# demo_IB2.net
KiCad netlist of a schematic drawn in EAGLE
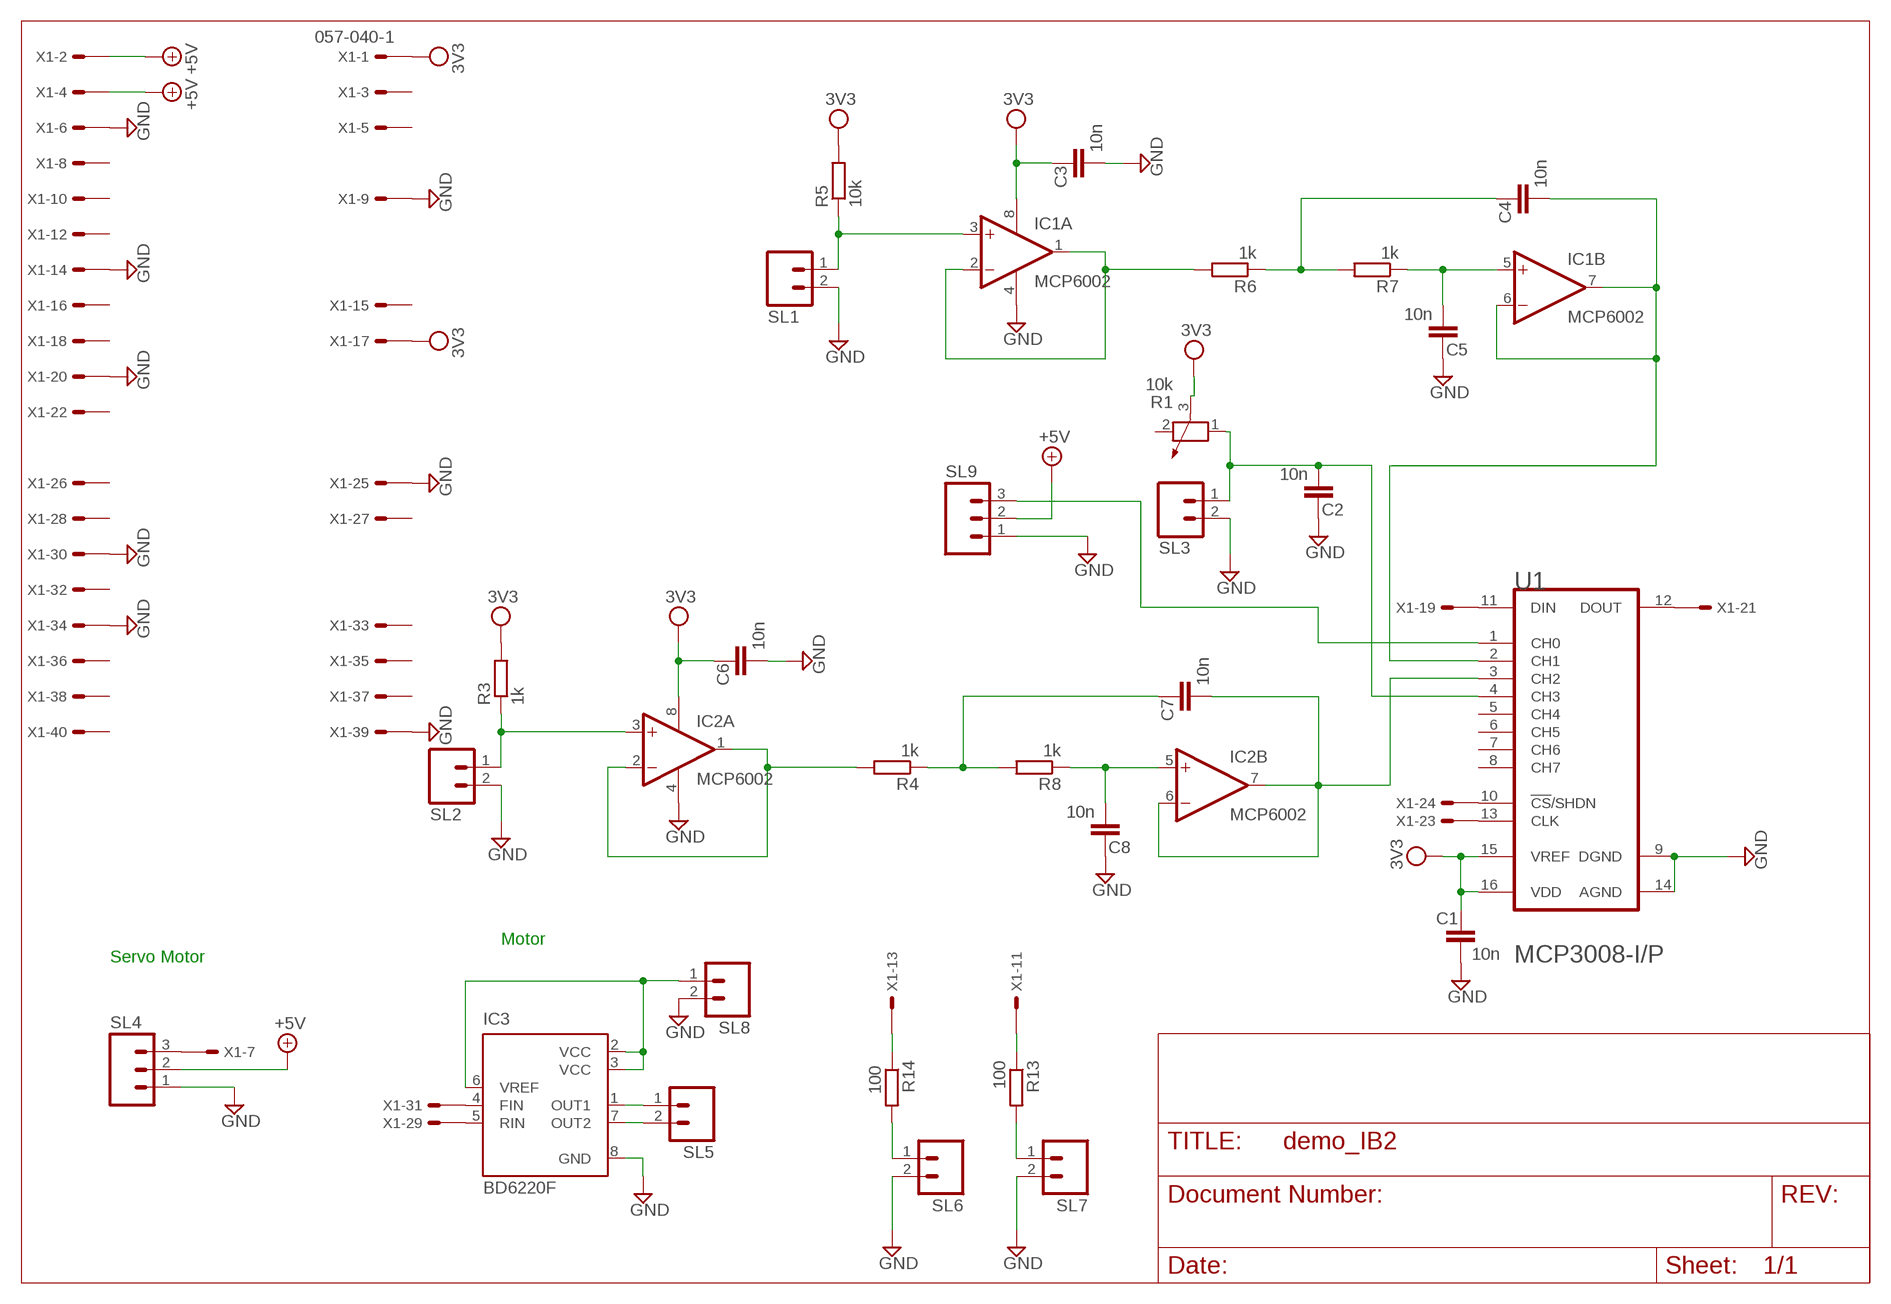
[diagram p0: schematic, sheet 1]

(export (version "E")
  (design (tool "Eeschema 10.0.6"))
  (components
    (comp (ref "C1")
      (value "10n")
      (footprint "eagle-import:C0805")
      (libsource (lib "eagle-import") (part "C-EUC0805"))
    )
    (comp (ref "C2")
      (value "10n")
      (footprint "eagle-import:C0805")
      (libsource (lib "eagle-import") (part "C-EUC0805"))
    )
    (comp (ref "C3")
      (value "10n")
      (footprint "eagle-import:C0805")
      (libsource (lib "eagle-import") (part "C-EUC0805"))
    )
    (comp (ref "C4")
      (value "10n")
      (footprint "eagle-import:C0805")
      (libsource (lib "eagle-import") (part "C-EUC0805"))
    )
    (comp (ref "C5")
      (value "10n")
      (footprint "eagle-import:C0805")
      (libsource (lib "eagle-import") (part "C-EUC0805"))
    )
    (comp (ref "C6")
      (value "10n")
      (footprint "eagle-import:C0805")
      (libsource (lib "eagle-import") (part "C-EUC0805"))
    )
    (comp (ref "C7")
      (value "10n")
      (footprint "eagle-import:C0805")
      (libsource (lib "eagle-import") (part "C-EUC0805"))
    )
    (comp (ref "C8")
      (value "10n")
      (footprint "eagle-import:C0805")
      (libsource (lib "eagle-import") (part "C-EUC0805"))
    )
    (comp (ref "IC1")
      (value "MCP6002")
      (footprint "eagle-import:SO08")
      (libsource (lib "eagle-import") (part "MCP602SN"))
    )
    (comp (ref "IC2")
      (value "MCP6002")
      (footprint "eagle-import:SO08")
      (libsource (lib "eagle-import") (part "MCP602SN"))
    )
    (comp (ref "IC3")
      (value "BD6220F")
      (footprint "eagle-import:SOP8")
      (libsource (lib "eagle-import") (part "BD6220F"))
    )
    (comp (ref "R1")
      (value "10k")
      (footprint "eagle-import:PT-10")
      (libsource (lib "eagle-import") (part "POTENTIOMETER_PT-10"))
    )
    (comp (ref "R3")
      (value "1k")
      (footprint "eagle-import:R0805")
      (libsource (lib "eagle-import") (part "R-EU_R0805"))
    )
    (comp (ref "R4")
      (value "1k")
      (footprint "eagle-import:R0805")
      (libsource (lib "eagle-import") (part "R-EU_R0805"))
    )
    (comp (ref "R5")
      (value "10k")
      (footprint "eagle-import:R0805")
      (libsource (lib "eagle-import") (part "R-EU_R0805"))
    )
    (comp (ref "R6")
      (value "1k")
      (footprint "eagle-import:R0805")
      (libsource (lib "eagle-import") (part "R-EU_R0805"))
    )
    (comp (ref "R7")
      (value "1k")
      (footprint "eagle-import:R0805")
      (libsource (lib "eagle-import") (part "R-EU_R0805"))
    )
    (comp (ref "R8")
      (value "1k")
      (footprint "eagle-import:R0805")
      (libsource (lib "eagle-import") (part "R-EU_R0805"))
    )
    (comp (ref "R13")
      (value "100")
      (footprint "eagle-import:R0805")
      (libsource (lib "eagle-import") (part "R-EU_R0805"))
    )
    (comp (ref "R14")
      (value "100")
      (footprint "eagle-import:R0805")
      (libsource (lib "eagle-import") (part "R-EU_R0805"))
    )
    (comp (ref "SL1")
      (value "M02")
      (footprint "eagle-import:02P")
      (libsource (lib "eagle-import") (part "M02"))
    )
    (comp (ref "SL2")
      (value "M02")
      (footprint "eagle-import:02P")
      (libsource (lib "eagle-import") (part "M02"))
    )
    (comp (ref "SL3")
      (value "M02")
      (footprint "eagle-import:02P")
      (libsource (lib "eagle-import") (part "M02"))
    )
    (comp (ref "SL4")
      (value "M03")
      (footprint "eagle-import:03P")
      (libsource (lib "eagle-import") (part "M03"))
    )
    (comp (ref "SL5")
      (value "M02")
      (footprint "eagle-import:02P")
      (libsource (lib "eagle-import") (part "M02"))
    )
    (comp (ref "SL6")
      (value "M02")
      (footprint "eagle-import:02P")
      (libsource (lib "eagle-import") (part "M02"))
    )
    (comp (ref "SL7")
      (value "M02")
      (footprint "eagle-import:02P")
      (libsource (lib "eagle-import") (part "M02"))
    )
    (comp (ref "SL8")
      (value "M02")
      (footprint "eagle-import:02P")
      (libsource (lib "eagle-import") (part "M02"))
    )
    (comp (ref "SL9")
      (value "M03")
      (footprint "eagle-import:03P")
      (libsource (lib "eagle-import") (part "M03"))
    )
    (comp (ref "U1")
      (value "MICROCHIP_MCP3008-I-P")
      (footprint "eagle-import:SO-16")
      (libsource (lib "eagle-import") (part "MICROCHIP_MCP3008-I-P"))
    )
    (comp (ref "X1")
      (value "057-040-1")
      (footprint "eagle-import:057-040-1")
      (libsource (lib "eagle-import") (part "057-040-1"))
    )
  )
  (nets
    (net (code "1") (name "+5V") (class "Default")
      (node (ref "SL4") (pin "2") (pinfunction "2_2") (pintype "passive"))
      (node (ref "SL9") (pin "2") (pinfunction "2_2") (pintype "passive"))
      (node (ref "X1") (pin "2") (pinfunction "S_2") (pintype "passive"))
      (node (ref "X1") (pin "4") (pinfunction "S_4") (pintype "passive"))
    )
    (net (code "2") (name "3V3") (class "Default")
      (node (ref "C1") (pin "1") (pinfunction "1_1") (pintype "passive"))
      (node (ref "C3") (pin "1") (pinfunction "1_1") (pintype "passive"))
      (node (ref "C6") (pin "1") (pinfunction "1_1") (pintype "passive"))
      (node (ref "IC1") (pin "8") (pinfunction "V+_8") (pintype "power_in"))
      (node (ref "IC2") (pin "8") (pinfunction "V+_8") (pintype "power_in"))
      (node (ref "R1") (pin "3") (pinfunction "3_3") (pintype "passive"))
      (node (ref "R3") (pin "2") (pinfunction "2_2") (pintype "passive"))
      (node (ref "R5") (pin "2") (pinfunction "2_2") (pintype "passive"))
      (node (ref "U1") (pin "15") (pinfunction "VREF_15") (pintype "input"))
      (node (ref "U1") (pin "16") (pinfunction "VDD_16") (pintype "power_in"))
      (node (ref "X1") (pin "1") (pinfunction "S_1") (pintype "passive"))
      (node (ref "X1") (pin "17") (pinfunction "S_17") (pintype "passive"))
    )
    (net (code "3") (name "GND") (class "Default")
      (node (ref "C1") (pin "2") (pinfunction "2_2") (pintype "passive"))
      (node (ref "C2") (pin "1") (pinfunction "1_1") (pintype "passive"))
      (node (ref "C3") (pin "2") (pinfunction "2_2") (pintype "passive"))
      (node (ref "C5") (pin "1") (pinfunction "1_1") (pintype "passive"))
      (node (ref "C6") (pin "2") (pinfunction "2_2") (pintype "passive"))
      (node (ref "C8") (pin "1") (pinfunction "1_1") (pintype "passive"))
      (node (ref "IC1") (pin "4") (pinfunction "V-_4") (pintype "power_in"))
      (node (ref "IC2") (pin "4") (pinfunction "V-_4") (pintype "power_in"))
      (node (ref "IC3") (pin "8") (pinfunction "GND_8") (pintype "power_in"))
      (node (ref "SL1") (pin "2") (pinfunction "2_2") (pintype "passive"))
      (node (ref "SL2") (pin "2") (pinfunction "2_2") (pintype "passive"))
      (node (ref "SL3") (pin "2") (pinfunction "2_2") (pintype "passive"))
      (node (ref "SL4") (pin "1") (pinfunction "1_1") (pintype "passive"))
      (node (ref "SL6") (pin "2") (pinfunction "2_2") (pintype "passive"))
      (node (ref "SL7") (pin "2") (pinfunction "2_2") (pintype "passive"))
      (node (ref "SL8") (pin "2") (pinfunction "2_2") (pintype "passive"))
      (node (ref "SL9") (pin "1") (pinfunction "1_1") (pintype "passive"))
      (node (ref "U1") (pin "14") (pinfunction "AGND_14") (pintype "power_in"))
      (node (ref "U1") (pin "9") (pinfunction "DGND_9") (pintype "power_in"))
      (node (ref "X1") (pin "14") (pinfunction "S_14") (pintype "passive"))
      (node (ref "X1") (pin "20") (pinfunction "S_20") (pintype "passive"))
      (node (ref "X1") (pin "25") (pinfunction "S_25") (pintype "passive"))
      (node (ref "X1") (pin "30") (pinfunction "S_30") (pintype "passive"))
      (node (ref "X1") (pin "34") (pinfunction "S_34") (pintype "passive"))
      (node (ref "X1") (pin "39") (pinfunction "S_39") (pintype "passive"))
      (node (ref "X1") (pin "6") (pinfunction "S_6") (pintype "passive"))
      (node (ref "X1") (pin "9") (pinfunction "S_9") (pintype "passive"))
    )
    (net (code "4") (name "Net-(C4-Pad1)") (class "Default")
      (node (ref "C4") (pin "1") (pinfunction "1_1") (pintype "passive"))
      (node (ref "R6") (pin "1") (pinfunction "1_1") (pintype "passive"))
      (node (ref "R7") (pin "2") (pinfunction "2_2") (pintype "passive"))
    )
    (net (code "5") (name "Net-(C7-Pad1)") (class "Default")
      (node (ref "C7") (pin "1") (pinfunction "1_1") (pintype "passive"))
      (node (ref "R4") (pin "1") (pinfunction "1_1") (pintype "passive"))
      (node (ref "R8") (pin "2") (pinfunction "2_2") (pintype "passive"))
    )
    (net (code "6") (name "Net-(IC1A-+IN)") (class "Default")
      (node (ref "IC1") (pin "3") (pinfunction "+IN_3") (pintype "input"))
      (node (ref "R5") (pin "1") (pinfunction "1_1") (pintype "passive"))
      (node (ref "SL1") (pin "1") (pinfunction "1_1") (pintype "passive"))
    )
    (net (code "7") (name "Net-(IC1A--IN)") (class "Default")
      (node (ref "IC1") (pin "1") (pinfunction "OUT_1") (pintype "output"))
      (node (ref "IC1") (pin "2") (pinfunction "-IN_2") (pintype "input"))
      (node (ref "R6") (pin "2") (pinfunction "2_2") (pintype "passive"))
    )
    (net (code "8") (name "Net-(IC1B-+IN)") (class "Default")
      (node (ref "C5") (pin "2") (pinfunction "2_2") (pintype "passive"))
      (node (ref "IC1") (pin "5") (pinfunction "+IN_5") (pintype "input"))
      (node (ref "R7") (pin "1") (pinfunction "1_1") (pintype "passive"))
    )
    (net (code "9") (name "Net-(IC1B--IN)") (class "Default")
      (node (ref "C4") (pin "2") (pinfunction "2_2") (pintype "passive"))
      (node (ref "IC1") (pin "6") (pinfunction "-IN_6") (pintype "input"))
      (node (ref "IC1") (pin "7") (pinfunction "OUT_7") (pintype "output"))
      (node (ref "U1") (pin "2") (pinfunction "CH1_2") (pintype "input"))
    )
    (net (code "10") (name "Net-(IC2A-+IN)") (class "Default")
      (node (ref "IC2") (pin "3") (pinfunction "+IN_3") (pintype "input"))
      (node (ref "R3") (pin "1") (pinfunction "1_1") (pintype "passive"))
      (node (ref "SL2") (pin "1") (pinfunction "1_1") (pintype "passive"))
    )
    (net (code "11") (name "Net-(IC2A--IN)") (class "Default")
      (node (ref "IC2") (pin "1") (pinfunction "OUT_1") (pintype "output"))
      (node (ref "IC2") (pin "2") (pinfunction "-IN_2") (pintype "input"))
      (node (ref "R4") (pin "2") (pinfunction "2_2") (pintype "passive"))
    )
    (net (code "12") (name "Net-(IC2B-+IN)") (class "Default")
      (node (ref "C8") (pin "2") (pinfunction "2_2") (pintype "passive"))
      (node (ref "IC2") (pin "5") (pinfunction "+IN_5") (pintype "input"))
      (node (ref "R8") (pin "1") (pinfunction "1_1") (pintype "passive"))
    )
    (net (code "13") (name "Net-(IC2B--IN)") (class "Default")
      (node (ref "C7") (pin "2") (pinfunction "2_2") (pintype "passive"))
      (node (ref "IC2") (pin "6") (pinfunction "-IN_6") (pintype "input"))
      (node (ref "IC2") (pin "7") (pinfunction "OUT_7") (pintype "output"))
      (node (ref "U1") (pin "3") (pinfunction "CH2_3") (pintype "input"))
    )
    (net (code "14") (name "Net-(IC3-FIN)") (class "Default")
      (node (ref "IC3") (pin "4") (pinfunction "FIN_4") (pintype "input"))
      (node (ref "X1") (pin "31") (pinfunction "S_31") (pintype "passive"))
    )
    (net (code "15") (name "Net-(IC3-OUT1)") (class "Default")
      (node (ref "IC3") (pin "1") (pinfunction "OUT1_1") (pintype "output"))
      (node (ref "SL5") (pin "1") (pinfunction "1_1") (pintype "passive"))
    )
    (net (code "16") (name "Net-(IC3-OUT2)") (class "Default")
      (node (ref "IC3") (pin "7") (pinfunction "OUT2_7") (pintype "output"))
      (node (ref "SL5") (pin "2") (pinfunction "2_2") (pintype "passive"))
    )
    (net (code "17") (name "Net-(IC3-RIN)") (class "Default")
      (node (ref "IC3") (pin "5") (pinfunction "RIN_5") (pintype "input"))
      (node (ref "X1") (pin "29") (pinfunction "S_29") (pintype "passive"))
    )
    (net (code "18") (name "Net-(IC3-VREF)") (class "Default")
      (node (ref "IC3") (pin "2") (pinfunction "VCC_2") (pintype "power_in"))
      (node (ref "IC3") (pin "3") (pinfunction "VCC_3") (pintype "power_in"))
      (node (ref "IC3") (pin "6") (pinfunction "VREF_6") (pintype "passive"))
      (node (ref "SL8") (pin "1") (pinfunction "1_1") (pintype "passive"))
    )
    (net (code "19") (name "Net-(R13-Pad2)") (class "Default")
      (node (ref "R13") (pin "2") (pinfunction "2_2") (pintype "passive"))
      (node (ref "SL7") (pin "1") (pinfunction "1_1") (pintype "passive"))
    )
    (net (code "20") (name "Net-(R14-Pad2)") (class "Default")
      (node (ref "R14") (pin "2") (pinfunction "2_2") (pintype "passive"))
      (node (ref "SL6") (pin "1") (pinfunction "1_1") (pintype "passive"))
    )
    (net (code "21") (name "Net-(U1-CH0)") (class "Default")
      (node (ref "SL9") (pin "3") (pinfunction "3_3") (pintype "passive"))
      (node (ref "U1") (pin "1") (pinfunction "CH0_1") (pintype "input"))
    )
    (net (code "22") (name "Net-(U1-CH3)") (class "Default")
      (node (ref "C2") (pin "2") (pinfunction "2_2") (pintype "passive"))
      (node (ref "R1") (pin "1") (pinfunction "1_1") (pintype "passive"))
      (node (ref "SL3") (pin "1") (pinfunction "1_1") (pintype "passive"))
      (node (ref "U1") (pin "4") (pinfunction "CH3_4") (pintype "input"))
    )
    (net (code "23") (name "Net-(U1-CLK)") (class "Default")
      (node (ref "U1") (pin "13") (pinfunction "CLK_13") (pintype "input"))
      (node (ref "X1") (pin "23") (pinfunction "S_23") (pintype "passive"))
    )
    (net (code "24") (name "Net-(U1-DIN)") (class "Default")
      (node (ref "U1") (pin "11") (pinfunction "DIN_11") (pintype "input"))
      (node (ref "X1") (pin "19") (pinfunction "S_19") (pintype "passive"))
    )
    (net (code "25") (name "Net-(U1-DOUT)") (class "Default")
      (node (ref "U1") (pin "12") (pinfunction "DOUT_12") (pintype "tri_state"))
      (node (ref "X1") (pin "21") (pinfunction "S_21") (pintype "passive"))
    )
    (net (code "26") (name "Net-(U1-~{CS}{slash}SHDN)") (class "Default")
      (node (ref "U1") (pin "10") (pinfunction "~{CS}/SHDN_10") (pintype "input"))
      (node (ref "X1") (pin "24") (pinfunction "S_24") (pintype "passive"))
    )
    (net (code "27") (name "Net-(X1AL-S)") (class "Default")
      (node (ref "SL4") (pin "3") (pinfunction "3_3") (pintype "passive"))
      (node (ref "X1") (pin "7") (pinfunction "S_7") (pintype "passive"))
    )
    (net (code "28") (name "Net-(X1C-S)") (class "Default")
      (node (ref "R13") (pin "1") (pinfunction "1_1") (pintype "passive"))
      (node (ref "X1") (pin "11") (pinfunction "S_11") (pintype "passive"))
    )
    (net (code "29") (name "Net-(X1E-S)") (class "Default")
      (node (ref "R14") (pin "1") (pinfunction "1_1") (pintype "passive"))
      (node (ref "X1") (pin "13") (pinfunction "S_13") (pintype "passive"))
    )
    (net (code "30") (name "unconnected-(R1-Pad2)") (class "Default")
      (node (ref "R1") (pin "2") (pinfunction "2_2") (pintype "passive"))
    )
    (net (code "31") (name "unconnected-(U1-CH4-Pad5)") (class "Default")
      (node (ref "U1") (pin "5") (pinfunction "CH4_5") (pintype "input"))
    )
    (net (code "32") (name "unconnected-(U1-CH5-Pad6)") (class "Default")
      (node (ref "U1") (pin "6") (pinfunction "CH5_6") (pintype "input"))
    )
    (net (code "33") (name "unconnected-(U1-CH6-Pad7)") (class "Default")
      (node (ref "U1") (pin "7") (pinfunction "CH6_7") (pintype "input"))
    )
    (net (code "34") (name "unconnected-(U1-CH7-Pad8)") (class "Default")
      (node (ref "U1") (pin "8") (pinfunction "CH7_8") (pintype "input"))
    )
    (net (code "35") (name "unconnected-(X1AA-S-Pad33)") (class "Default")
      (node (ref "X1") (pin "33") (pinfunction "S_33") (pintype "passive"))
    )
    (net (code "36") (name "unconnected-(X1AC-S-Pad35)") (class "Default")
      (node (ref "X1") (pin "35") (pinfunction "S_35") (pintype "passive"))
    )
    (net (code "37") (name "unconnected-(X1AD-S-Pad36)") (class "Default")
      (node (ref "X1") (pin "36") (pinfunction "S_36") (pintype "passive"))
    )
    (net (code "38") (name "unconnected-(X1AE-S-Pad37)") (class "Default")
      (node (ref "X1") (pin "37") (pinfunction "S_37") (pintype "passive"))
    )
    (net (code "39") (name "unconnected-(X1AF-S-Pad38)") (class "Default")
      (node (ref "X1") (pin "38") (pinfunction "S_38") (pintype "passive"))
    )
    (net (code "40") (name "unconnected-(X1AI-S-Pad40)") (class "Default")
      (node (ref "X1") (pin "40") (pinfunction "S_40") (pintype "passive"))
    )
    (net (code "41") (name "unconnected-(X1AJ-S-Pad5)") (class "Default")
      (node (ref "X1") (pin "5") (pinfunction "S_5") (pintype "passive"))
    )
    (net (code "42") (name "unconnected-(X1AM-S-Pad8)") (class "Default")
      (node (ref "X1") (pin "8") (pinfunction "S_8") (pintype "passive"))
    )
    (net (code "43") (name "unconnected-(X1B-S-Pad10)") (class "Default")
      (node (ref "X1") (pin "10") (pinfunction "S_10") (pintype "passive"))
    )
    (net (code "44") (name "unconnected-(X1D-S-Pad12)") (class "Default")
      (node (ref "X1") (pin "12") (pinfunction "S_12") (pintype "passive"))
    )
    (net (code "45") (name "unconnected-(X1G-S-Pad15)") (class "Default")
      (node (ref "X1") (pin "15") (pinfunction "S_15") (pintype "passive"))
    )
    (net (code "46") (name "unconnected-(X1H-S-Pad16)") (class "Default")
      (node (ref "X1") (pin "16") (pinfunction "S_16") (pintype "passive"))
    )
    (net (code "47") (name "unconnected-(X1J-S-Pad18)") (class "Default")
      (node (ref "X1") (pin "18") (pinfunction "S_18") (pintype "passive"))
    )
    (net (code "48") (name "unconnected-(X1O-S-Pad22)") (class "Default")
      (node (ref "X1") (pin "22") (pinfunction "S_22") (pintype "passive"))
    )
    (net (code "49") (name "unconnected-(X1S-S-Pad26)") (class "Default")
      (node (ref "X1") (pin "26") (pinfunction "S_26") (pintype "passive"))
    )
    (net (code "50") (name "unconnected-(X1T-S-Pad27)") (class "Default")
      (node (ref "X1") (pin "27") (pinfunction "S_27") (pintype "passive"))
    )
    (net (code "51") (name "unconnected-(X1U-S-Pad28)") (class "Default")
      (node (ref "X1") (pin "28") (pinfunction "S_28") (pintype "passive"))
    )
    (net (code "52") (name "unconnected-(X1W-S-Pad3)") (class "Default")
      (node (ref "X1") (pin "3") (pinfunction "S_3") (pintype "passive"))
    )
    (net (code "53") (name "unconnected-(X1Z-S-Pad32)") (class "Default")
      (node (ref "X1") (pin "32") (pinfunction "S_32") (pintype "passive"))
    )
  )
)
